# charger_module.net
KiCad netlist of a schematic drawn in EAGLE
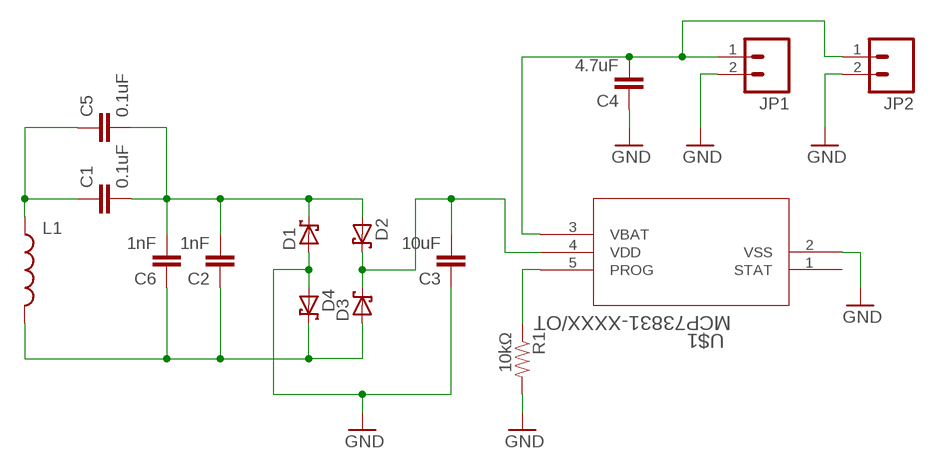
[diagram p0: schematic, sheet 1]

(export (version "E")
  (design (tool "Eeschema 10.0.6"))
  (components
    (comp (ref "C1")
      (value "0.1uF")
      (footprint "eagle-import:CAP-PTH-5MM")
      (libsource (lib "eagle-import") (part "CAPPTH1"))
    )
    (comp (ref "C2")
      (value "1nF")
      (footprint "eagle-import:CAP-PTH-5MM")
      (libsource (lib "eagle-import") (part "CAPPTH1"))
    )
    (comp (ref "C3")
      (value "10uF")
      (footprint "eagle-import:CAP-PTH-5MM")
      (libsource (lib "eagle-import") (part "CAPPTH1"))
    )
    (comp (ref "C4")
      (value "4.7uF")
      (footprint "eagle-import:CAP-PTH-5MM")
      (libsource (lib "eagle-import") (part "CAPPTH1"))
    )
    (comp (ref "C5")
      (value "0.1uF")
      (footprint "eagle-import:CAP-PTH-5MM")
      (libsource (lib "eagle-import") (part "CAPPTH1"))
    )
    (comp (ref "C6")
      (value "1nF")
      (footprint "eagle-import:CAP-PTH-5MM")
      (libsource (lib "eagle-import") (part "CAPPTH1"))
    )
    (comp (ref "D1")
      (value "SCHOTTKY-DIODECB417-15")
      (footprint "eagle-import:CB417-15")
      (libsource (lib "eagle-import") (part "SCHOTTKY-DIODECB417-15"))
    )
    (comp (ref "D2")
      (value "SCHOTTKY-DIODECB417-15")
      (footprint "eagle-import:CB417-15")
      (libsource (lib "eagle-import") (part "SCHOTTKY-DIODECB417-15"))
    )
    (comp (ref "D3")
      (value "SCHOTTKY-DIODECB417-15")
      (footprint "eagle-import:CB417-15")
      (libsource (lib "eagle-import") (part "SCHOTTKY-DIODECB417-15"))
    )
    (comp (ref "D4")
      (value "SCHOTTKY-DIODECB417-15")
      (footprint "eagle-import:CB417-15")
      (libsource (lib "eagle-import") (part "SCHOTTKY-DIODECB417-15"))
    )
    (comp (ref "JP1")
      (value "M02PTH")
      (footprint "eagle-import:1X02")
      (libsource (lib "eagle-import") (part "M02PTH"))
    )
    (comp (ref "JP2")
      (value "M02PTH")
      (footprint "eagle-import:1X02")
      (libsource (lib "eagle-import") (part "M02PTH"))
    )
    (comp (ref "L1")
      (value "INDUCTORAXIAL-0.6")
      (footprint "eagle-import:AXIAL-0.6")
      (libsource (lib "eagle-import") (part "INDUCTORAXIAL-0.6"))
    )
    (comp (ref "R1")
      (value "10kΩ")
      (footprint "eagle-import:AXIAL-0.3")
      (libsource (lib "eagle-import") (part "RESISTORAXIAL-0.3"))
    )
    (comp (ref "U$1")
      (value "MCP73831-XXXX/OT")
      (footprint "eagle-import:SOT-23-5_MC")
      (libsource (lib "eagle-import") (part "MCP73831-XXXX/OT"))
    )
  )
  (nets
    (net (code "1") (name "GND") (class "Default")
      (node (ref "C3") (pin "1") (pinfunction "1_1") (pintype "passive"))
      (node (ref "C4") (pin "1") (pinfunction "1_1") (pintype "passive"))
      (node (ref "D1") (pin "A") (pinfunction "A_A") (pintype "passive"))
      (node (ref "D4") (pin "A") (pinfunction "A_A") (pintype "passive"))
      (node (ref "JP1") (pin "2") (pinfunction "2_2") (pintype "passive"))
      (node (ref "JP2") (pin "2") (pinfunction "2_2") (pintype "passive"))
      (node (ref "R1") (pin "P$2") (pinfunction "2_P$2") (pintype "passive"))
      (node (ref "U$1") (pin "2") (pinfunction "VSS_2") (pintype "passive"))
    )
    (net (code "2") (name "Net-(C1-Pad2)") (class "Default")
      (node (ref "C1") (pin "2") (pinfunction "2_2") (pintype "passive"))
      (node (ref "C2") (pin "2") (pinfunction "2_2") (pintype "passive"))
      (node (ref "C5") (pin "2") (pinfunction "2_2") (pintype "passive"))
      (node (ref "C6") (pin "2") (pinfunction "2_2") (pintype "passive"))
      (node (ref "D1") (pin "C") (pinfunction "C_C") (pintype "passive"))
      (node (ref "D2") (pin "A") (pinfunction "A_A") (pintype "passive"))
    )
    (net (code "3") (name "Net-(L1-1)") (class "Default")
      (node (ref "C1") (pin "1") (pinfunction "1_1") (pintype "passive"))
      (node (ref "C5") (pin "1") (pinfunction "1_1") (pintype "passive"))
      (node (ref "L1") (pin "P$1") (pinfunction "1_P$1") (pintype "passive"))
    )
    (net (code "4") (name "Net-(L1-2)") (class "Default")
      (node (ref "C2") (pin "1") (pinfunction "1_1") (pintype "passive"))
      (node (ref "C6") (pin "1") (pinfunction "1_1") (pintype "passive"))
      (node (ref "D3") (pin "A") (pinfunction "A_A") (pintype "passive"))
      (node (ref "D4") (pin "C") (pinfunction "C_C") (pintype "passive"))
      (node (ref "L1") (pin "P$2") (pinfunction "2_P$2") (pintype "passive"))
    )
    (net (code "5") (name "Net-(R1-1)") (class "Default")
      (node (ref "R1") (pin "P$1") (pinfunction "1_P$1") (pintype "passive"))
      (node (ref "U$1") (pin "5") (pinfunction "PROG_5") (pintype "passive"))
    )
    (net (code "6") (name "Net-(U$1-VBAT)") (class "Default")
      (node (ref "C4") (pin "2") (pinfunction "2_2") (pintype "passive"))
      (node (ref "JP1") (pin "1") (pinfunction "1_1") (pintype "passive"))
      (node (ref "JP2") (pin "1") (pinfunction "1_1") (pintype "passive"))
      (node (ref "U$1") (pin "3") (pinfunction "VBAT_3") (pintype "passive"))
    )
    (net (code "7") (name "Net-(U$1-VDD)") (class "Default")
      (node (ref "C3") (pin "2") (pinfunction "2_2") (pintype "passive"))
      (node (ref "D2") (pin "C") (pinfunction "C_C") (pintype "passive"))
      (node (ref "D3") (pin "C") (pinfunction "C_C") (pintype "passive"))
      (node (ref "U$1") (pin "4") (pinfunction "VDD_4") (pintype "passive"))
    )
    (net (code "8") (name "unconnected-(U$1-STAT-Pad1)") (class "Default")
      (node (ref "U$1") (pin "1") (pinfunction "STAT_1") (pintype "passive"))
    )
  )
)
